# ESP32LiPoUSB.net
KiCad netlist of a schematic drawn in EAGLE
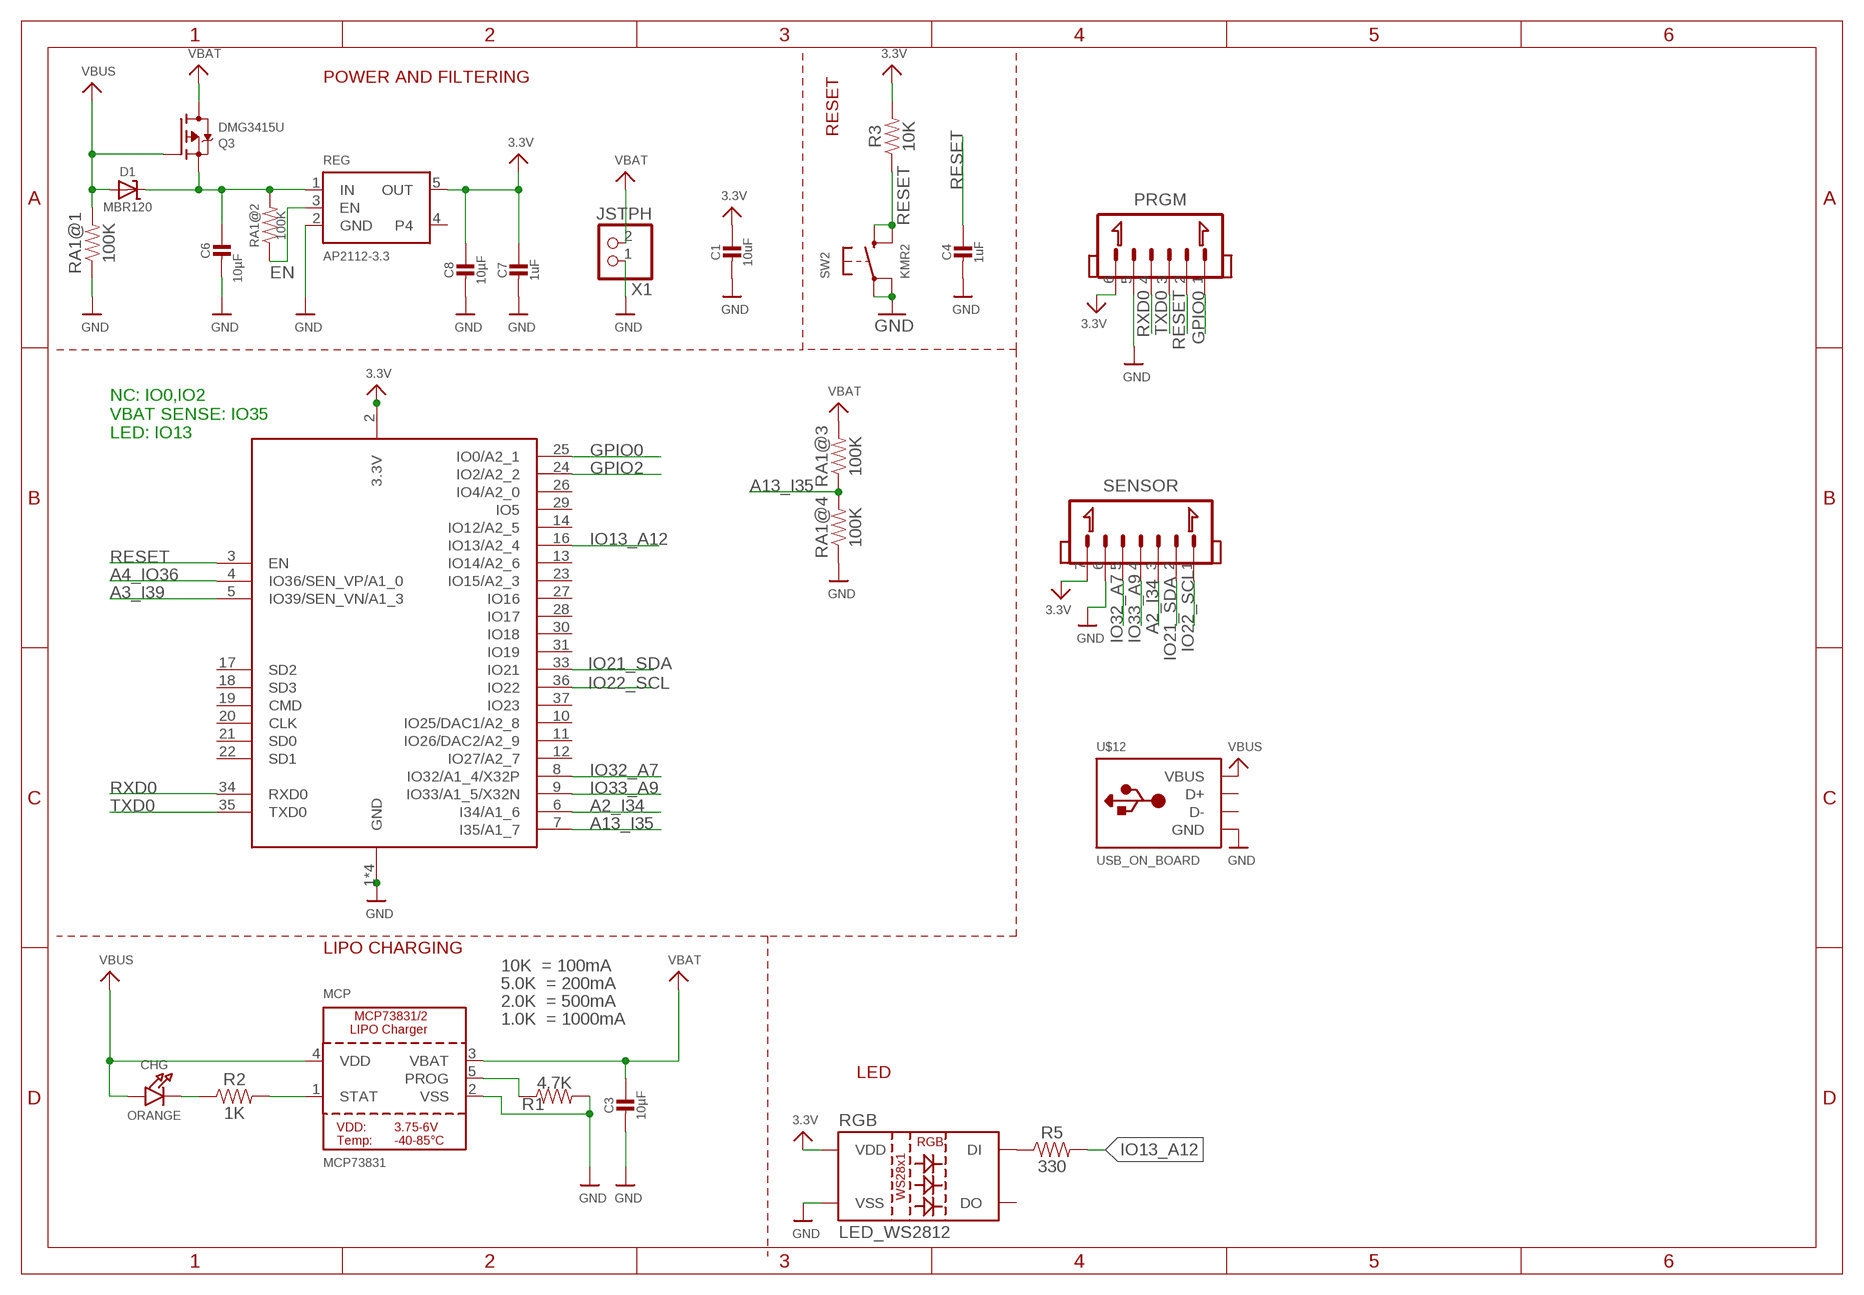
[diagram p0: schematic, sheet 1]

(export (version "E")
  (design (tool "Eeschema 10.0.6"))
  (components
    (comp (ref "C1")
      (value "10uF")
      (footprint "eagle-import:CAP_0805")
      (libsource (lib "eagle-import") (part "CAP_CERAMIC_0805"))
    )
    (comp (ref "C3")
      (value "10µF")
      (footprint "eagle-import:CAP_0805")
      (libsource (lib "eagle-import") (part "CAP_CERAMIC_0805"))
    )
    (comp (ref "C4")
      (value "1uF")
      (footprint "eagle-import:CAP_0603")
      (libsource (lib "eagle-import") (part "CAP_CERAMIC_0603"))
    )
    (comp (ref "C6")
      (value "10µF")
      (footprint "eagle-import:CAP_0603")
      (libsource (lib "eagle-import") (part "CAP_CERAMIC_0603"))
    )
    (comp (ref "C7")
      (value "1uF")
      (footprint "eagle-import:CAP_0603")
      (libsource (lib "eagle-import") (part "CAP_CERAMIC_0603"))
    )
    (comp (ref "C8")
      (value "10µF")
      (footprint "eagle-import:CAP_0805")
      (libsource (lib "eagle-import") (part "CAP_CERAMIC_0805"))
    )
    (comp (ref "CHG")
      (value "ORANGE")
      (footprint "eagle-import:MICROBUILDER_CHIPLED_0603")
      (libsource (lib "eagle-import") (part "LED0603"))
    )
    (comp (ref "D1")
      (value "MBR120")
      (footprint "eagle-import:SOD-123")
      (libsource (lib "eagle-import") (part "DIODE-SCHOTTKYSOD-123"))
    )
    (comp (ref "MCP")
      (value "MCP73831")
      (footprint "eagle-import:SOT23-5")
      (libsource (lib "eagle-import") (part "MCP73831/2"))
    )
    (comp (ref "PRGM")
      (value "JST_1.25_6P")
      (footprint "eagle-import:JST1.25_6P")
      (libsource (lib "eagle-import") (part "JST_1.25_6P"))
    )
    (comp (ref "Q3")
      (value "DMG3415U")
      (footprint "eagle-import:SOT23-R")
      (libsource (lib "eagle-import") (part "MOSFET-P"))
    )
    (comp (ref "R1")
      (value "4.7K")
      (footprint "eagle-import:0603")
      (libsource (lib "eagle-import") (part "RESISTOR0603"))
    )
    (comp (ref "R2")
      (value "1K")
      (footprint "eagle-import:0603")
      (libsource (lib "eagle-import") (part "RESISTOR0603"))
    )
    (comp (ref "R3")
      (value "10K")
      (footprint "eagle-import:0603")
      (libsource (lib "eagle-import") (part "RESISTOR0603"))
    )
    (comp (ref "R5")
      (value "330")
      (footprint "eagle-import:0603")
      (libsource (lib "eagle-import") (part "RESISTOR0603"))
    )
    (comp (ref "RA1")
      (value "100K")
      (footprint "eagle-import:RESCAF80P320X160X60-8N")
      (libsource (lib "eagle-import") (part "RESISTOR_ARRAY_1206_SEPARATE"))
    )
    (comp (ref "REG")
      (value "AP2112-3.3")
      (footprint "eagle-import:SOT23-5")
      (libsource (lib "eagle-import") (part "VREG_SOT23-5"))
    )
    (comp (ref "RGB")
      (value "LED_WS2812")
      (footprint "eagle-import:LED-TRICOLOR-5050-IC")
      (libsource (lib "eagle-import") (part "LED_WS2812"))
    )
    (comp (ref "SENSOR")
      (value "JST_1.25_7P")
      (footprint "eagle-import:JST1.25_7P")
      (libsource (lib "eagle-import") (part "JST_1.25_7P"))
    )
    (comp (ref "SW2")
      (value "KMR2")
      (footprint "eagle-import:BTN_KMR2_4.6X2.8")
      (libsource (lib "eagle-import") (part "SWITCH_TACT_SMT4.6X2.8"))
    )
    (comp (ref "U$12")
      (value "USB_ON_BOARD")
      (footprint "eagle-import:USB_ON_BOARD")
      (libsource (lib "eagle-import") (part "USB_ON_BOARD"))
    )
    (comp (ref "X1")
      (value "JSTPH")
      (footprint "eagle-import:JSTPH2")
      (libsource (lib "eagle-import") (part "CON_JST_PH_2PIN"))
    )
    (comp (ref "X2")
      (value "ESP32_WROOM32_SKINNY")
      (footprint "eagle-import:WROOM32_SKINNY")
      (libsource (lib "eagle-import") (part "ESP32_WROOM32_SKINNY"))
    )
  )
  (nets
    (net (code "1") (name "/A2_I34") (class "Default")
      (node (ref "SENSOR") (pin "3") (pinfunction "3_3") (pintype "passive"))
      (node (ref "X2") (pin "6") (pinfunction "I34/A1_6_6") (pintype "bidirectional"))
    )
    (net (code "2") (name "/A3_I39") (class "Default")
      (node (ref "X2") (pin "5") (pinfunction "IO39/SEN_VN/A1_3_5") (pintype "passive"))
    )
    (net (code "3") (name "/A4_IO36") (class "Default")
      (node (ref "X2") (pin "4") (pinfunction "IO36/SEN_VP/A1_0_4") (pintype "passive"))
    )
    (net (code "4") (name "/A13_I35") (class "Default")
      (node (ref "RA1") (pin "3") (pinfunction "1_3") (pintype "passive"))
      (node (ref "RA1") (pin "8") (pinfunction "2_8") (pintype "passive"))
      (node (ref "X2") (pin "7") (pinfunction "I35/A1_7_7") (pintype "bidirectional"))
    )
    (net (code "5") (name "/EN") (class "Default")
      (node (ref "RA1") (pin "2") (pinfunction "1_2") (pintype "passive"))
      (node (ref "REG") (pin "3") (pinfunction "EN_3") (pintype "input"))
    )
    (net (code "6") (name "/GPIO0") (class "Default")
      (node (ref "PRGM") (pin "1") (pinfunction "1_1") (pintype "passive"))
      (node (ref "X2") (pin "25") (pinfunction "IO0/A2_1_25") (pintype "bidirectional"))
    )
    (net (code "7") (name "/GPIO2") (class "Default")
      (node (ref "X2") (pin "24") (pinfunction "IO2/A2_2_24") (pintype "bidirectional"))
    )
    (net (code "8") (name "/IO21_SDA") (class "Default")
      (node (ref "SENSOR") (pin "2") (pinfunction "2_2") (pintype "passive"))
      (node (ref "X2") (pin "33") (pinfunction "IO21_33") (pintype "bidirectional"))
    )
    (net (code "9") (name "/IO22_SCL") (class "Default")
      (node (ref "SENSOR") (pin "1") (pinfunction "1_1") (pintype "passive"))
      (node (ref "X2") (pin "36") (pinfunction "IO22_36") (pintype "bidirectional"))
    )
    (net (code "10") (name "/IO32_A7") (class "Default")
      (node (ref "SENSOR") (pin "5") (pinfunction "5_5") (pintype "passive"))
      (node (ref "X2") (pin "8") (pinfunction "IO32/A1_4/X32P_8") (pintype "bidirectional"))
    )
    (net (code "11") (name "/IO33_A9") (class "Default")
      (node (ref "SENSOR") (pin "4") (pinfunction "4_4") (pintype "passive"))
      (node (ref "X2") (pin "9") (pinfunction "IO33/A1_5/X32N_9") (pintype "bidirectional"))
    )
    (net (code "12") (name "/RESET") (class "Default")
      (node (ref "C4") (pin "1") (pinfunction "1_1") (pintype "passive"))
      (node (ref "PRGM") (pin "2") (pinfunction "2_2") (pintype "passive"))
      (node (ref "R3") (pin "1") (pinfunction "1_1") (pintype "passive"))
      (node (ref "SW2") (pin "B") (pinfunction "S_B") (pintype "passive"))
      (node (ref "SW2") (pin "B'") (pinfunction "S1_B'") (pintype "passive"))
      (node (ref "X2") (pin "3") (pinfunction "EN_3") (pintype "input"))
    )
    (net (code "13") (name "/RXD0") (class "Default")
      (node (ref "PRGM") (pin "4") (pinfunction "4_4") (pintype "passive"))
      (node (ref "X2") (pin "34") (pinfunction "RXD0_34") (pintype "input"))
    )
    (net (code "14") (name "/TXD0") (class "Default")
      (node (ref "PRGM") (pin "3") (pinfunction "3_3") (pintype "passive"))
      (node (ref "X2") (pin "35") (pinfunction "TXD0_35") (pintype "output"))
    )
    (net (code "15") (name "3.3V") (class "Default")
      (node (ref "C1") (pin "1") (pinfunction "1_1") (pintype "passive"))
      (node (ref "C7") (pin "1") (pinfunction "1_1") (pintype "passive"))
      (node (ref "C8") (pin "1") (pinfunction "1_1") (pintype "passive"))
      (node (ref "PRGM") (pin "6") (pinfunction "6_6") (pintype "passive"))
      (node (ref "R3") (pin "2") (pinfunction "2_2") (pintype "passive"))
      (node (ref "REG") (pin "5") (pinfunction "OUT_5") (pintype "power_in"))
      (node (ref "RGB") (pin "VDD") (pinfunction "VDD_VDD") (pintype "bidirectional"))
      (node (ref "SENSOR") (pin "7") (pinfunction "7_7") (pintype "passive"))
      (node (ref "X2") (pin "2") (pinfunction "3.3V_2") (pintype "passive"))
    )
    (net (code "16") (name "GND") (class "Default")
      (node (ref "C1") (pin "2") (pinfunction "2_2") (pintype "passive"))
      (node (ref "C3") (pin "2") (pinfunction "2_2") (pintype "passive"))
      (node (ref "C4") (pin "2") (pinfunction "2_2") (pintype "passive"))
      (node (ref "C6") (pin "2") (pinfunction "2_2") (pintype "passive"))
      (node (ref "C7") (pin "2") (pinfunction "2_2") (pintype "passive"))
      (node (ref "C8") (pin "2") (pinfunction "2_2") (pintype "passive"))
      (node (ref "MCP") (pin "2") (pinfunction "VSS_2") (pintype "power_in"))
      (node (ref "PRGM") (pin "5") (pinfunction "5_5") (pintype "passive"))
      (node (ref "R1") (pin "2") (pinfunction "2_2") (pintype "passive"))
      (node (ref "RA1") (pin "1") (pinfunction "1_1") (pintype "passive"))
      (node (ref "RA1") (pin "4") (pinfunction "1_4") (pintype "passive"))
      (node (ref "REG") (pin "2") (pinfunction "GND_2") (pintype "power_in"))
      (node (ref "RGB") (pin "VSS") (pinfunction "VSS_VSS") (pintype "bidirectional"))
      (node (ref "SENSOR") (pin "6") (pinfunction "6_6") (pintype "passive"))
      (node (ref "SW2") (pin "A") (pinfunction "P_A") (pintype "passive"))
      (node (ref "SW2") (pin "A'") (pinfunction "P1_A'") (pintype "passive"))
      (node (ref "U$12") (pin "GND") (pinfunction "GND_GND") (pintype "power_in"))
      (node (ref "X1") (pin "1") (pinfunction "1_1") (pintype "passive"))
      (node (ref "X2") (pin "1") (pinfunction "GND_1") (pintype "passive"))
      (node (ref "X2") (pin "15") (pinfunction "GND_15") (pintype "passive"))
      (node (ref "X2") (pin "38") (pinfunction "GND_38") (pintype "passive"))
      (node (ref "X2") (pin "P$1") (pinfunction "GND_P$1") (pintype "passive"))
    )
    (net (code "17") (name "IO13_A12") (class "Default")
      (node (ref "R5") (pin "2") (pinfunction "2_2") (pintype "passive"))
      (node (ref "X2") (pin "16") (pinfunction "IO13/A2_4_16") (pintype "bidirectional"))
    )
    (net (code "18") (name "Net-(CHG-PadC)") (class "Default")
      (node (ref "CHG") (pin "C") (pinfunction "C_C") (pintype "passive"))
      (node (ref "R2") (pin "1") (pinfunction "1_1") (pintype "passive"))
    )
    (net (code "19") (name "Net-(MCP-PROG)") (class "Default")
      (node (ref "MCP") (pin "5") (pinfunction "PROG_5") (pintype "input"))
      (node (ref "R1") (pin "1") (pinfunction "1_1") (pintype "passive"))
    )
    (net (code "20") (name "Net-(MCP-STAT)") (class "Default")
      (node (ref "MCP") (pin "1") (pinfunction "STAT_1") (pintype "output"))
      (node (ref "R2") (pin "2") (pinfunction "2_2") (pintype "passive"))
    )
    (net (code "21") (name "Net-(Q3-S)") (class "Default")
      (node (ref "C6") (pin "1") (pinfunction "1_1") (pintype "passive"))
      (node (ref "D1") (pin "C") (pinfunction "C_C") (pintype "passive"))
      (node (ref "Q3") (pin "2") (pinfunction "S_2") (pintype "passive"))
      (node (ref "RA1") (pin "6") (pinfunction "2_6") (pintype "passive"))
      (node (ref "REG") (pin "1") (pinfunction "IN_1") (pintype "power_in"))
    )
    (net (code "22") (name "Net-(RGB-DI)") (class "Default")
      (node (ref "R5") (pin "1") (pinfunction "1_1") (pintype "passive"))
      (node (ref "RGB") (pin "DIN") (pinfunction "DI_DIN") (pintype "bidirectional"))
    )
    (net (code "23") (name "VBAT") (class "Default")
      (node (ref "C3") (pin "1") (pinfunction "1_1") (pintype "passive"))
      (node (ref "MCP") (pin "3") (pinfunction "VBAT_3") (pintype "power_in"))
      (node (ref "Q3") (pin "3") (pinfunction "D_3") (pintype "passive"))
      (node (ref "RA1") (pin "7") (pinfunction "2_7") (pintype "passive"))
      (node (ref "X1") (pin "2") (pinfunction "2_2") (pintype "passive"))
    )
    (net (code "24") (name "VBUS") (class "Default")
      (node (ref "CHG") (pin "A") (pinfunction "A_A") (pintype "passive"))
      (node (ref "D1") (pin "A") (pinfunction "A_A") (pintype "passive"))
      (node (ref "MCP") (pin "4") (pinfunction "VDD_4") (pintype "power_in"))
      (node (ref "Q3") (pin "1") (pinfunction "G_1") (pintype "passive"))
      (node (ref "RA1") (pin "5") (pinfunction "2_5") (pintype "passive"))
      (node (ref "U$12") (pin "VCC") (pinfunction "VBUS_VCC") (pintype "power_in"))
    )
    (net (code "25") (name "unconnected-(REG-P4-Pad4)") (class "Default")
      (node (ref "REG") (pin "4") (pinfunction "P4_4") (pintype "bidirectional"))
    )
    (net (code "26") (name "unconnected-(RGB-DO-PadDOUT)") (class "Default")
      (node (ref "RGB") (pin "DOUT") (pinfunction "DO_DOUT") (pintype "bidirectional"))
    )
    (net (code "27") (name "unconnected-(U$12-PadD+)") (class "Default")
      (node (ref "U$12") (pin "D+") (pinfunction "D+_D+") (pintype "bidirectional"))
    )
    (net (code "28") (name "unconnected-(U$12-PadD-)") (class "Default")
      (node (ref "U$12") (pin "D-") (pinfunction "D-_D-") (pintype "bidirectional"))
    )
    (net (code "29") (name "unconnected-(X2-CLK-Pad20)") (class "Default")
      (node (ref "X2") (pin "20") (pinfunction "CLK_20") (pintype "bidirectional"))
    )
    (net (code "30") (name "unconnected-(X2-CMD-Pad19)") (class "Default")
      (node (ref "X2") (pin "19") (pinfunction "CMD_19") (pintype "bidirectional"))
    )
    (net (code "31") (name "unconnected-(X2-IO4{slash}A2_0-Pad26)") (class "Default")
      (node (ref "X2") (pin "26") (pinfunction "IO4/A2_0_26") (pintype "bidirectional"))
    )
    (net (code "32") (name "unconnected-(X2-IO5-Pad29)") (class "Default")
      (node (ref "X2") (pin "29") (pinfunction "IO5_29") (pintype "bidirectional"))
    )
    (net (code "33") (name "unconnected-(X2-IO12{slash}A2_5-Pad14)") (class "Default")
      (node (ref "X2") (pin "14") (pinfunction "IO12/A2_5_14") (pintype "bidirectional"))
    )
    (net (code "34") (name "unconnected-(X2-IO14{slash}A2_6-Pad13)") (class "Default")
      (node (ref "X2") (pin "13") (pinfunction "IO14/A2_6_13") (pintype "bidirectional"))
    )
    (net (code "35") (name "unconnected-(X2-IO15{slash}A2_3-Pad23)") (class "Default")
      (node (ref "X2") (pin "23") (pinfunction "IO15/A2_3_23") (pintype "bidirectional"))
    )
    (net (code "36") (name "unconnected-(X2-IO16-Pad27)") (class "Default")
      (node (ref "X2") (pin "27") (pinfunction "IO16_27") (pintype "bidirectional"))
    )
    (net (code "37") (name "unconnected-(X2-IO17-Pad28)") (class "Default")
      (node (ref "X2") (pin "28") (pinfunction "IO17_28") (pintype "bidirectional"))
    )
    (net (code "38") (name "unconnected-(X2-IO18-Pad30)") (class "Default")
      (node (ref "X2") (pin "30") (pinfunction "IO18_30") (pintype "bidirectional"))
    )
    (net (code "39") (name "unconnected-(X2-IO19-Pad31)") (class "Default")
      (node (ref "X2") (pin "31") (pinfunction "IO19_31") (pintype "bidirectional"))
    )
    (net (code "40") (name "unconnected-(X2-IO23-Pad37)") (class "Default")
      (node (ref "X2") (pin "37") (pinfunction "IO23_37") (pintype "bidirectional"))
    )
    (net (code "41") (name "unconnected-(X2-IO25{slash}DAC1{slash}A2_8-Pad10)") (class "Default")
      (node (ref "X2") (pin "10") (pinfunction "IO25/DAC1/A2_8_10") (pintype "bidirectional"))
    )
    (net (code "42") (name "unconnected-(X2-IO26{slash}DAC2{slash}A2_9-Pad11)") (class "Default")
      (node (ref "X2") (pin "11") (pinfunction "IO26/DAC2/A2_9_11") (pintype "bidirectional"))
    )
    (net (code "43") (name "unconnected-(X2-IO27{slash}A2_7-Pad12)") (class "Default")
      (node (ref "X2") (pin "12") (pinfunction "IO27/A2_7_12") (pintype "bidirectional"))
    )
    (net (code "44") (name "unconnected-(X2-SD0-Pad21)") (class "Default")
      (node (ref "X2") (pin "21") (pinfunction "SD0_21") (pintype "bidirectional"))
    )
    (net (code "45") (name "unconnected-(X2-SD1-Pad22)") (class "Default")
      (node (ref "X2") (pin "22") (pinfunction "SD1_22") (pintype "bidirectional"))
    )
    (net (code "46") (name "unconnected-(X2-SD2-Pad17)") (class "Default")
      (node (ref "X2") (pin "17") (pinfunction "SD2_17") (pintype "bidirectional"))
    )
    (net (code "47") (name "unconnected-(X2-SD3-Pad18)") (class "Default")
      (node (ref "X2") (pin "18") (pinfunction "SD3_18") (pintype "bidirectional"))
    )
  )
)
